# Power.net
KiCad netlist of a schematic drawn in Altium Designer
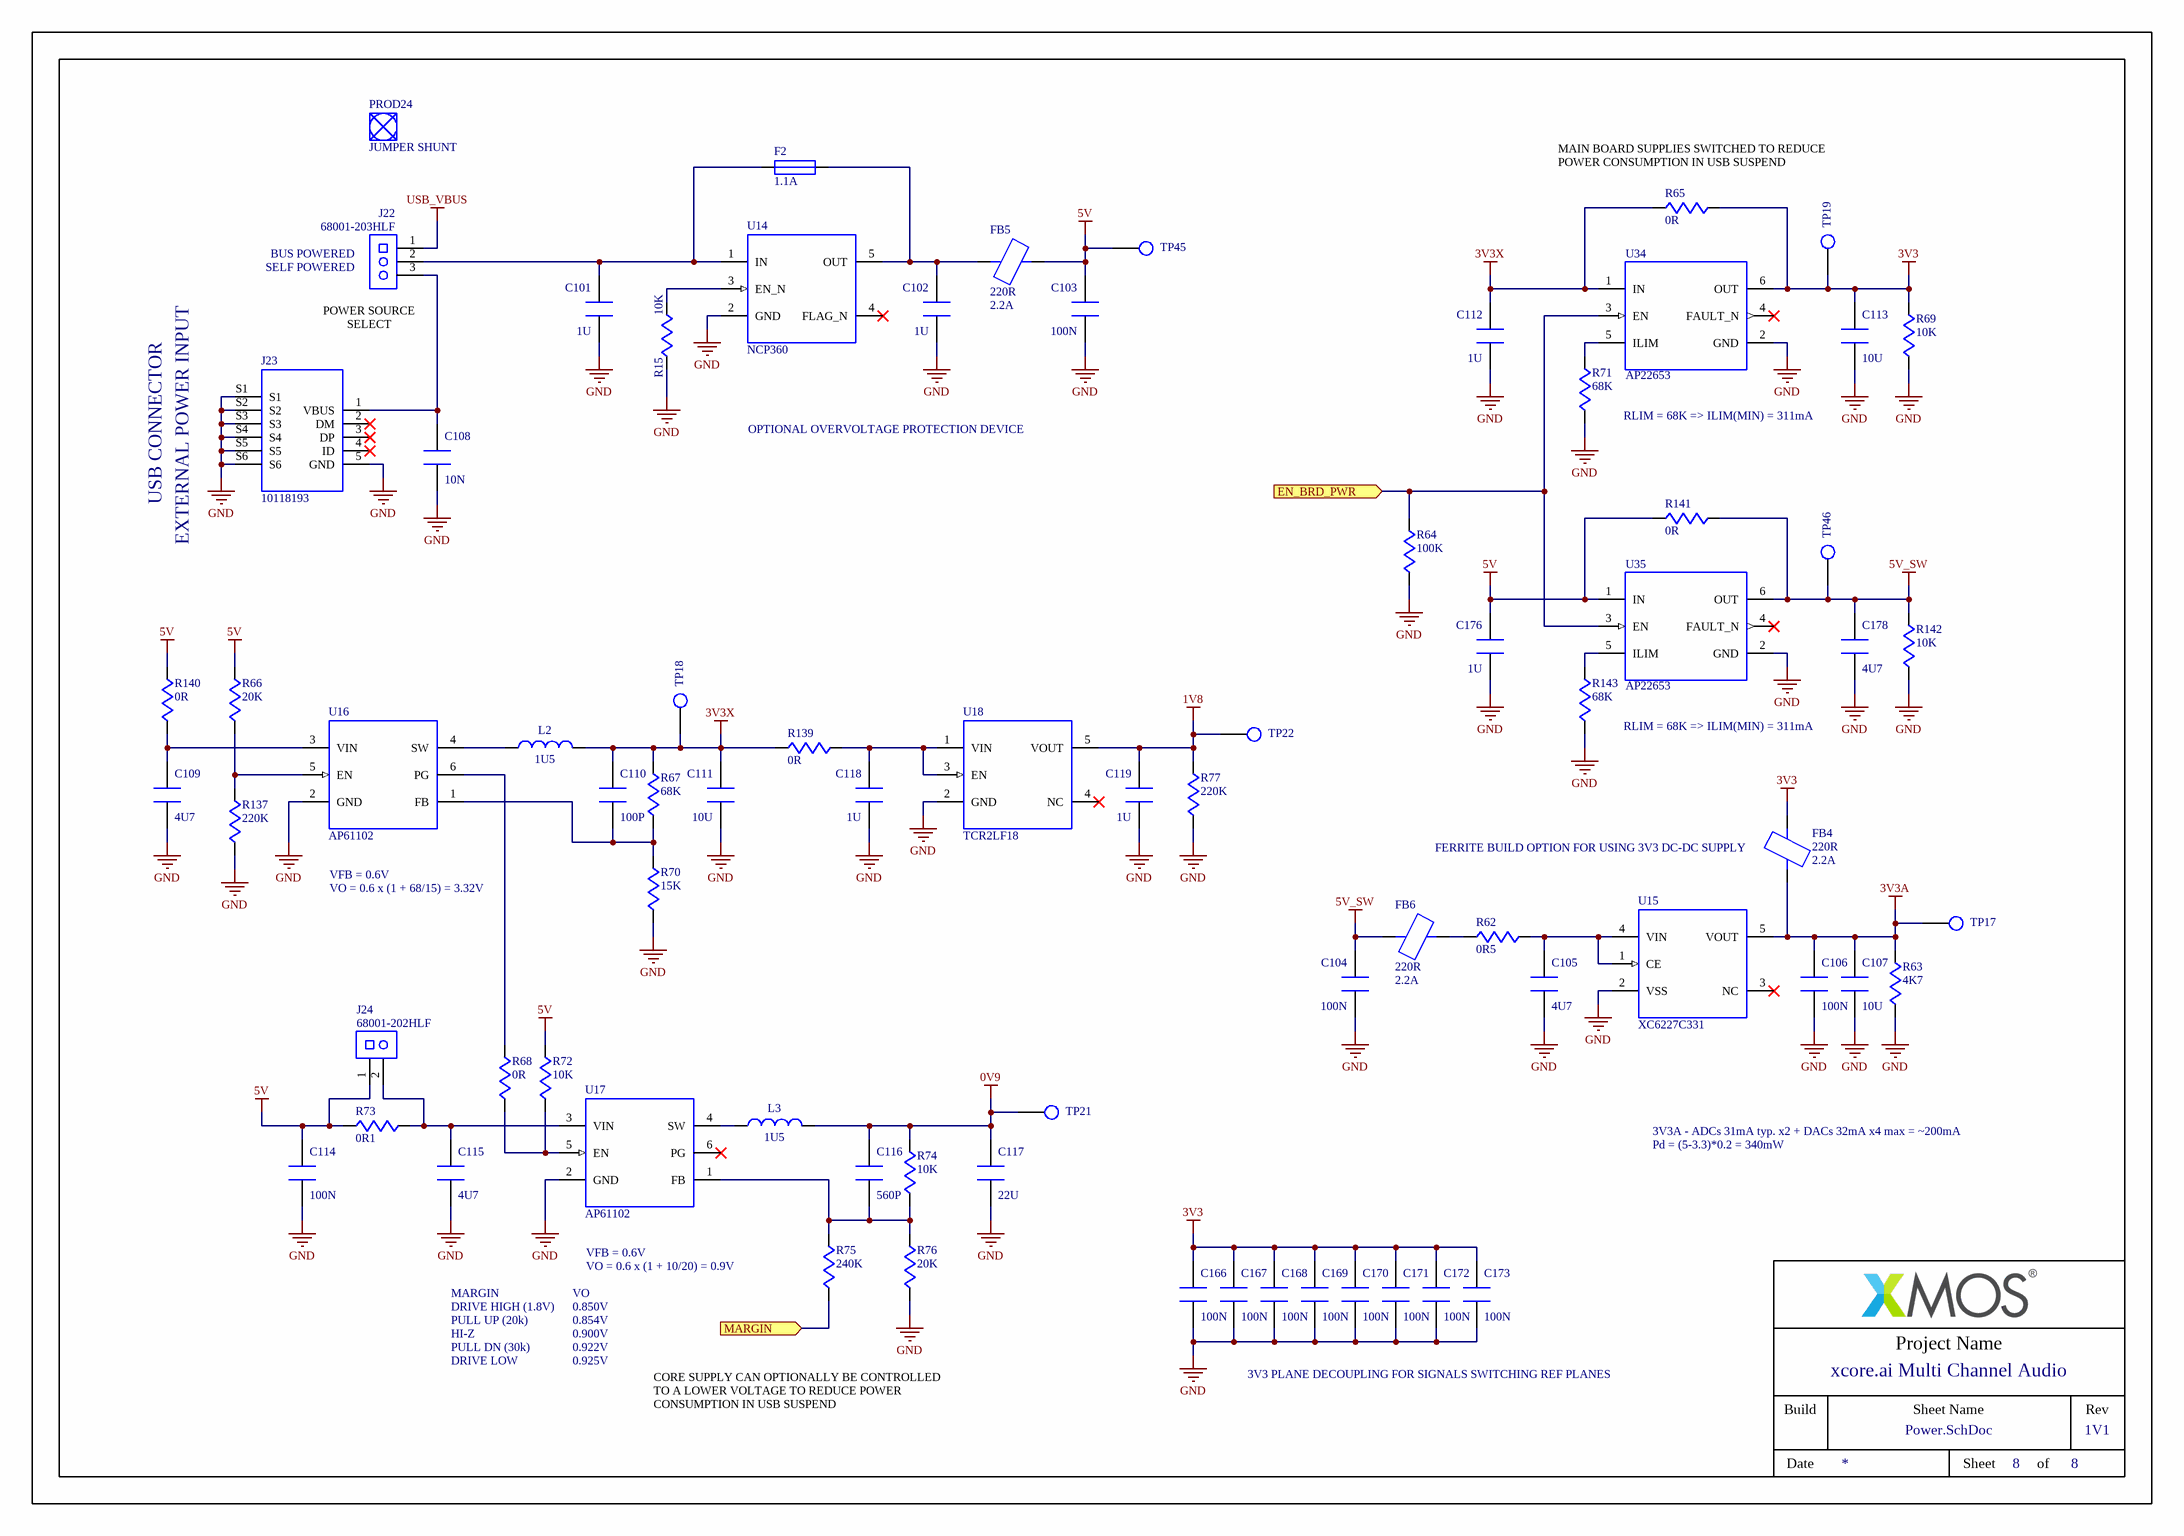
[diagram p0: Power.SchDoc]

(export (version "E")
  (design (tool "Eeschema 10.0.6"))
  (components
    (comp (ref "C101")
      (value "1U")
      (footprint "CAPC1005X55N")
      (description "CHIP CAPACITOR, CERAMIC, 1.0UF, 16V, 10%, X5R, 0402")
      (fields (field (name "PART NUMBER") "STD-06-0140") (field (name "TOLERANCE") "20%"))
      (libsource (lib "JG_StandardLibrary") (part "CAP_NP"))
    )
    (comp (ref "C102")
      (value "1U")
      (footprint "CAPC1005X55N")
      (description "CHIP CAPACITOR, CERAMIC, 1.0UF, 16V, 10%, X5R, 0402")
      (fields (field (name "PART NUMBER") "STD-06-0140") (field (name "TOLERANCE") "20%"))
      (libsource (lib "JG_StandardLibrary") (part "CAP_NP"))
    )
    (comp (ref "C103")
      (value "100N")
      (footprint "CAPC1005X55N")
      (description "CHIP CAPACITOR, CERAMIC, 100NF, 16V, 10%, X7R, 0402")
      (fields (field (name "PART NUMBER") "STD-06-0048") (field (name "TOLERANCE") "10%"))
      (libsource (lib "JG_StandardLibrary") (part "CAP_NP"))
    )
    (comp (ref "C104")
      (value "100N")
      (footprint "CAPC1005X55N")
      (description "CHIP CAPACITOR, CERAMIC, 100NF, 16V, 10%, X7R, 0402")
      (fields (field (name "PART NUMBER") "STD-06-0048") (field (name "TOLERANCE") "10%"))
      (libsource (lib "JG_StandardLibrary") (part "CAP_NP"))
    )
    (comp (ref "C105")
      (value "4U7")
      (footprint "CAPC1608X90N")
      (description "CHIP CAPACITOR, CERAMIC, 4.7UF, 16V, 10%, X5R, 0603")
      (fields (field (name "PART NUMBER") "STD-06-0151") (field (name "TOLERANCE") "10%"))
      (libsource (lib "JG_StandardLibrary") (part "CAP_NP"))
    )
    (comp (ref "C106")
      (value "100N")
      (footprint "CAPC1005X55N")
      (description "CHIP CAPACITOR, CERAMIC, 100NF, 16V, 10%, X7R, 0402")
      (fields (field (name "PART NUMBER") "STD-06-0048") (field (name "TOLERANCE") "10%"))
      (libsource (lib "JG_StandardLibrary") (part "CAP_NP"))
    )
    (comp (ref "C107")
      (value "10U")
      (footprint "CAPC1608X90N")
      (description "CHIP CAPACITOR, CERAMIC, 10UF, 10V, 20%, X5R, 0603")
      (fields (field (name "PART NUMBER") "GEN-03-0043") (field (name "TOLERANCE") "20%"))
      (libsource (lib "JG_GeneralLibrary") (part "CAP_NP"))
    )
    (comp (ref "C108")
      (value "10N")
      (footprint "CAPC1005X55N")
      (description "CHIP CAPACITOR, CERAMIC, 10NF, 50V, 10%, X7R, 0402")
      (fields (field (name "PART NUMBER") "STD-06-0042") (field (name "TOLERANCE") "10%"))
      (libsource (lib "JG_StandardLibrary") (part "CAP_NP"))
    )
    (comp (ref "C109")
      (value "4U7")
      (footprint "CAPC1608X90N")
      (description "CHIP CAPACITOR, CERAMIC, 4.7UF, 16V, 10%, X5R, 0603")
      (fields (field (name "PART NUMBER") "STD-06-0151") (field (name "TOLERANCE") "10%"))
      (libsource (lib "JG_StandardLibrary") (part "CAP_NP"))
    )
    (comp (ref "C110")
      (value "100P")
      (footprint "CAPC1005X55N")
      (description "CHIP CAPACITOR, CERAMIC, 100PF, 50V, 10%, X7R, 0402")
      (fields (field (name "PART NUMBER") "STD-06-0030") (field (name "TOLERANCE") "10%"))
      (libsource (lib "JG_StandardLibrary") (part "CAP_NP"))
    )
    (comp (ref "C111")
      (value "10U")
      (footprint "CAPC1608X90N")
      (description "CHIP CAPACITOR, CERAMIC, 10UF, 10V, 20%, X5R, 0603")
      (fields (field (name "PART NUMBER") "GEN-03-0043") (field (name "TOLERANCE") "20%"))
      (libsource (lib "JG_GeneralLibrary") (part "CAP_NP"))
    )
    (comp (ref "C112")
      (value "1U")
      (footprint "CAPC1005X55N")
      (description "CHIP CAPACITOR, CERAMIC, 1.0UF, 16V, 10%, X5R, 0402")
      (fields (field (name "PART NUMBER") "STD-06-0140") (field (name "TOLERANCE") "20%"))
      (libsource (lib "JG_StandardLibrary") (part "CAP_NP"))
    )
    (comp (ref "C113")
      (value "10U")
      (footprint "CAPC1608X90N")
      (description "CHIP CAPACITOR, CERAMIC, 10UF, 10V, 20%, X5R, 0603")
      (fields (field (name "PART NUMBER") "GEN-03-0043") (field (name "TOLERANCE") "20%"))
      (libsource (lib "JG_GeneralLibrary") (part "CAP_NP"))
    )
    (comp (ref "C114")
      (value "100N")
      (footprint "CAPC1005X55N")
      (description "CHIP CAPACITOR, CERAMIC, 100NF, 16V, 10%, X7R, 0402")
      (fields (field (name "PART NUMBER") "STD-06-0048") (field (name "TOLERANCE") "10%"))
      (libsource (lib "JG_StandardLibrary") (part "CAP_NP"))
    )
    (comp (ref "C115")
      (value "4U7")
      (footprint "CAPC1608X90N")
      (description "CHIP CAPACITOR, CERAMIC, 4.7UF, 16V, 10%, X5R, 0603")
      (fields (field (name "PART NUMBER") "STD-06-0151") (field (name "TOLERANCE") "10%"))
      (libsource (lib "JG_StandardLibrary") (part "CAP_NP"))
    )
    (comp (ref "C116")
      (value "560P")
      (footprint "CAPC1005X55N")
      (description "CHIP CAPACITOR, CERAMIC, 560PF, 50V, 5%, NP0, 0402")
      (fields (field (name "PART NUMBER") "STD-06-0147") (field (name "TOLERANCE") "5%"))
      (libsource (lib "JG_StandardLibrary") (part "CAP_NP"))
    )
    (comp (ref "C117")
      (value "22U")
      (footprint "CAPC1608X90N")
      (description "CHIP CAPACITOR, CERAMIC, 22UF, 6.3V, 20%, X5R, 0603")
      (fields (field (name "PART NUMBER") "GEN-03-0046") (field (name "TOLERANCE") "20%"))
      (libsource (lib "JG_GeneralLibrary") (part "CAP_NP"))
    )
    (comp (ref "C118")
      (value "1U")
      (footprint "CAPC1005X55N")
      (description "CHIP CAPACITOR, CERAMIC, 1.0UF, 16V, 10%, X5R, 0402")
      (fields (field (name "PART NUMBER") "STD-06-0140") (field (name "TOLERANCE") "20%"))
      (libsource (lib "JG_StandardLibrary") (part "CAP_NP"))
    )
    (comp (ref "C119")
      (value "1U")
      (footprint "CAPC1005X55N")
      (description "CHIP CAPACITOR, CERAMIC, 1.0UF, 16V, 10%, X5R, 0402")
      (fields (field (name "PART NUMBER") "STD-06-0140") (field (name "TOLERANCE") "20%"))
      (libsource (lib "JG_StandardLibrary") (part "CAP_NP"))
    )
    (comp (ref "C166")
      (value "100N")
      (footprint "CAPC1005X55N")
      (description "CHIP CAPACITOR, CERAMIC, 100NF, 16V, 10%, X7R, 0402")
      (fields (field (name "PART NUMBER") "STD-06-0048") (field (name "TOLERANCE") "10%"))
      (libsource (lib "JG_StandardLibrary") (part "CAP_NP"))
    )
    (comp (ref "C167")
      (value "100N")
      (footprint "CAPC1005X55N")
      (description "CHIP CAPACITOR, CERAMIC, 100NF, 16V, 10%, X7R, 0402")
      (fields (field (name "PART NUMBER") "STD-06-0048") (field (name "TOLERANCE") "10%"))
      (libsource (lib "JG_StandardLibrary") (part "CAP_NP"))
    )
    (comp (ref "C168")
      (value "100N")
      (footprint "CAPC1005X55N")
      (description "CHIP CAPACITOR, CERAMIC, 100NF, 16V, 10%, X7R, 0402")
      (fields (field (name "PART NUMBER") "STD-06-0048") (field (name "TOLERANCE") "10%"))
      (libsource (lib "JG_StandardLibrary") (part "CAP_NP"))
    )
    (comp (ref "C169")
      (value "100N")
      (footprint "CAPC1005X55N")
      (description "CHIP CAPACITOR, CERAMIC, 100NF, 16V, 10%, X7R, 0402")
      (fields (field (name "PART NUMBER") "STD-06-0048") (field (name "TOLERANCE") "10%"))
      (libsource (lib "JG_StandardLibrary") (part "CAP_NP"))
    )
    (comp (ref "C170")
      (value "100N")
      (footprint "CAPC1005X55N")
      (description "CHIP CAPACITOR, CERAMIC, 100NF, 16V, 10%, X7R, 0402")
      (fields (field (name "PART NUMBER") "STD-06-0048") (field (name "TOLERANCE") "10%"))
      (libsource (lib "JG_StandardLibrary") (part "CAP_NP"))
    )
    (comp (ref "C171")
      (value "100N")
      (footprint "CAPC1005X55N")
      (description "CHIP CAPACITOR, CERAMIC, 100NF, 16V, 10%, X7R, 0402")
      (fields (field (name "PART NUMBER") "STD-06-0048") (field (name "TOLERANCE") "10%"))
      (libsource (lib "JG_StandardLibrary") (part "CAP_NP"))
    )
    (comp (ref "C172")
      (value "100N")
      (footprint "CAPC1005X55N")
      (description "CHIP CAPACITOR, CERAMIC, 100NF, 16V, 10%, X7R, 0402")
      (fields (field (name "PART NUMBER") "STD-06-0048") (field (name "TOLERANCE") "10%"))
      (libsource (lib "JG_StandardLibrary") (part "CAP_NP"))
    )
    (comp (ref "C173")
      (value "100N")
      (footprint "CAPC1005X55N")
      (description "CHIP CAPACITOR, CERAMIC, 100NF, 16V, 10%, X7R, 0402")
      (fields (field (name "PART NUMBER") "STD-06-0048") (field (name "TOLERANCE") "10%"))
      (libsource (lib "JG_StandardLibrary") (part "CAP_NP"))
    )
    (comp (ref "C176")
      (value "1U")
      (footprint "CAPC1005X55N")
      (description "CHIP CAPACITOR, CERAMIC, 1.0UF, 16V, 10%, X5R, 0402")
      (fields (field (name "PART NUMBER") "STD-06-0140") (field (name "TOLERANCE") "20%"))
      (libsource (lib "JG_StandardLibrary") (part "CAP_NP"))
    )
    (comp (ref "C178")
      (value "4U7")
      (footprint "CAPC1608X90N")
      (description "CHIP CAPACITOR, CERAMIC, 4.7UF, 16V, 10%, X5R, 0603")
      (fields (field (name "PART NUMBER") "STD-06-0151") (field (name "TOLERANCE") "10%"))
      (libsource (lib "JG_StandardLibrary") (part "CAP_NP"))
    )
    (comp (ref "F2")
      (value "1.1A")
      (footprint "FUSC4632X150N")
      (description "Polyswitch Resettable Fuse, miniSMDC Series, 1.1A, 24V, SMD")
      (fields (field (name "PART NUMBER") "GEN-21-0008") (field (name "MANUFACTURER") "Littelfuse"))
      (libsource (lib "JG_GeneralLibrary") (part "FUSE"))
    )
    (comp (ref "FB4")
      (value "220R")
      (footprint "INDC1608X95N")
      (description "Ferrite Bead, 220R AT 100MHz, For Power Lines, AEC-Q200, 0603, 2.2A")
      (fields
        (field (name "PART NUMBER") "GEN-04-0018")
        (field (name "RATED CURRENT") "2.2A")
        (field (name "MANUFACTURER") "Murata")
      )
      (libsource (lib "JG_GeneralLibrary") (part "FERRITE"))
    )
    (comp (ref "FB5")
      (value "220R")
      (footprint "INDC1608X95N")
      (description "Ferrite Bead, 220R AT 100MHz, For Power Lines, AEC-Q200, 0603, 2.2A")
      (fields
        (field (name "PART NUMBER") "GEN-04-0018")
        (field (name "RATED CURRENT") "2.2A")
        (field (name "MANUFACTURER") "Murata")
      )
      (libsource (lib "JG_GeneralLibrary") (part "FERRITE"))
    )
    (comp (ref "FB6")
      (value "220R")
      (footprint "INDC1608X95N")
      (description "Ferrite Bead, 220R AT 100MHz, For Power Lines, AEC-Q200, 0603, 2.2A")
      (fields
        (field (name "PART NUMBER") "GEN-04-0018")
        (field (name "RATED CURRENT") "2.2A")
        (field (name "MANUFACTURER") "Murata")
      )
      (libsource (lib "JG_GeneralLibrary") (part "FERRITE"))
    )
    (comp (ref "J22")
      (value "68001-203HLF")
      (footprint "HDR_FCI_68001_203")
      (description "Pin Header, Male, Vertical, Through Hole, 3 Way, 1x3, 0.1 Inch Pitch")
      (fields (field (name "PART NUMBER") "GEN-01-0023") (field (name "MANUFACTURER") "FCI"))
      (libsource (lib "JG_GeneralLibrary") (part "PIN_HEADER_1X3"))
    )
    (comp (ref "J23")
      (value "10118193")
      (footprint "CON_FCI_10118193")
      (description "USB Micro B Receptacle, Right Angle, SMD w/2 DIP Legs")
      (fields (field (name "PART NUMBER") "GEN-01-0020") (field (name "MANUFACTURER") "FCI"))
      (libsource (lib "JG_GeneralLibrary") (part "FCI_10118193"))
    )
    (comp (ref "J24")
      (value "68001-202HLF")
      (footprint "HDR_FCI_68001_202")
      (description "Pin Header, Male, Vertical, Through Hole, 2 Way, 1x2, 0.1 Inch Pitch")
      (fields (field (name "PART NUMBER") "GEN-01-0011") (field (name "MANUFACTURER") "FCI"))
      (libsource (lib "JG_GeneralLibrary") (part "PIN_HEADER_1X2"))
    )
    (comp (ref "L2")
      (value "1U5")
      (footprint "INDC2520X120N")
      (description "Power Inductor, 1.5uH, 2.6A, 65mR DCR, 2.5x2.0x1.2mm, SMD")
      (fields (field (name "PART NUMBER") "GEN-05-0025") (field (name "TOLERANCE") "20%"))
      (libsource (lib "JG_GeneralLibrary") (part "INDUCTOR"))
    )
    (comp (ref "L3")
      (value "1U5")
      (footprint "INDC2520X120N")
      (description "Power Inductor, 1.5uH, 2.6A, 65mR DCR, 2.5x2.0x1.2mm, SMD")
      (fields (field (name "PART NUMBER") "GEN-05-0025") (field (name "TOLERANCE") "20%"))
      (libsource (lib "JG_GeneralLibrary") (part "INDUCTOR"))
    )
    (comp (ref "PROD24")
      (value "JUMPER SHUNT")
      (description "Jumper Shunt, Single Circuit, Open Type, 2.54mm Pitch, 6mm High, Gold Flash")
      (fields (field (name "PART NUMBER") "GEN-23-0011") (field (name "MANUFACTURER") "Sullins"))
      (libsource (lib "JG_GeneralLibrary") (part "PROD_ITEM"))
    )
    (comp (ref "R15")
      (value "10K")
      (footprint "RESC1608X55N")
      (description "CHIP RESISTOR, 10K OHM, 0.1W, 1%, 0603")
      (fields (field (name "PART NUMBER") "STD-02-0086") (field (name "TOLERANCE") "1%"))
      (libsource (lib "JG_StandardLibrary") (part "RES"))
    )
    (comp (ref "R62")
      (value "0R5")
      (footprint "RESC1608X55N")
      (description "CHIP RESISTOR, 0.5 OHM, 100mW, 1%, 0603")
      (fields (field (name "PART NUMBER") "GEN-02-0023") (field (name "TOLERANCE") "1%"))
      (libsource (lib "JG_GeneralLibrary") (part "RES"))
    )
    (comp (ref "R63")
      (value "4K7")
      (footprint "RESC1608X55N")
      (description "CHIP RESISTOR, 4.7K OHM, 0.1W, 1%, 0603")
      (fields (field (name "PART NUMBER") "STD-02-0078") (field (name "TOLERANCE") "1%"))
      (libsource (lib "JG_StandardLibrary") (part "RES"))
    )
    (comp (ref "R64")
      (value "100K")
      (footprint "RESC1608X55N")
      (description "CHIP RESISTOR, 100K OHM, 0.1W, 1%, 0603")
      (fields (field (name "PART NUMBER") "STD-02-0110") (field (name "TOLERANCE") "1%"))
      (libsource (lib "JG_StandardLibrary") (part "RES"))
    )
    (comp (ref "R65")
      (value "0R")
      (footprint "RESC1608X55N")
      (description "CHIP RESISTOR, ZERO OHM JUMPER, 1A, 0603")
      (fields (field (name "PART NUMBER") "STD-02-0001") (field (name "TOLERANCE") "NA"))
      (libsource (lib "JG_StandardLibrary") (part "RES"))
    )
    (comp (ref "R66")
      (value "20K")
      (footprint "RESC1608X55N")
      (description "CHIP RESISTOR, 20K OHM, 0.1W, 1%, 0603")
      (fields (field (name "PART NUMBER") "STD-02-0093") (field (name "TOLERANCE") "1%"))
      (libsource (lib "JG_StandardLibrary") (part "RES"))
    )
    (comp (ref "R67")
      (value "68K")
      (footprint "RESC1608X55N")
      (description "CHIP RESISTOR, 68K OHM, 0.1W, 1%, 0603")
      (fields (field (name "PART NUMBER") "STD-02-0106") (field (name "TOLERANCE") "1%"))
      (libsource (lib "JG_StandardLibrary") (part "RES"))
    )
    (comp (ref "R68")
      (value "0R")
      (footprint "RESC1608X55N")
      (description "CHIP RESISTOR, ZERO OHM JUMPER, 1A, 0603")
      (fields (field (name "PART NUMBER") "STD-02-0001") (field (name "TOLERANCE") "NA"))
      (libsource (lib "JG_StandardLibrary") (part "RES"))
    )
    (comp (ref "R69")
      (value "10K")
      (footprint "RESC1608X55N")
      (description "CHIP RESISTOR, 10K OHM, 0.1W, 1%, 0603")
      (fields (field (name "PART NUMBER") "STD-02-0086") (field (name "TOLERANCE") "1%"))
      (libsource (lib "JG_StandardLibrary") (part "RES"))
    )
    (comp (ref "R70")
      (value "15K")
      (footprint "RESC1608X55N")
      (description "CHIP RESISTOR, 15K OHM, 0.1W, 1%, 0603")
      (fields (field (name "PART NUMBER") "STD-02-0090") (field (name "TOLERANCE") "1%"))
      (libsource (lib "JG_StandardLibrary") (part "RES"))
    )
    (comp (ref "R71")
      (value "68K")
      (footprint "RESC1608X55N")
      (description "CHIP RESISTOR, 68K OHM, 0.1W, 1%, 0603")
      (fields (field (name "PART NUMBER") "STD-02-0106") (field (name "TOLERANCE") "1%"))
      (libsource (lib "JG_StandardLibrary") (part "RES"))
    )
    (comp (ref "R72")
      (value "10K")
      (footprint "RESC1608X55N")
      (description "CHIP RESISTOR, 10K OHM, 0.1W, 1%, 0603")
      (fields (field (name "PART NUMBER") "STD-02-0086") (field (name "TOLERANCE") "1%"))
      (libsource (lib "JG_StandardLibrary") (part "RES"))
    )
    (comp (ref "R73")
      (value "0R1")
      (footprint "RESC1608X55N")
      (description "CHIP RESISTOR, 0.1 OHM, 100mW, 1%, 0603")
      (fields (field (name "PART NUMBER") "GEN-02-0024") (field (name "TOLERANCE") "1%"))
      (libsource (lib "JG_GeneralLibrary") (part "RES"))
    )
    (comp (ref "R74")
      (value "10K")
      (footprint "RESC1608X55N")
      (description "CHIP RESISTOR, 10K OHM, 0.1W, 1%, 0603")
      (fields (field (name "PART NUMBER") "STD-02-0086") (field (name "TOLERANCE") "1%"))
      (libsource (lib "JG_StandardLibrary") (part "RES"))
    )
    (comp (ref "R75")
      (value "240K")
      (footprint "RESC1608X55N")
      (description "CHIP RESISTOR, 240K OHM, 0.1W, 1%, 0603")
      (fields (field (name "PART NUMBER") "STD-02-0119") (field (name "TOLERANCE") "1%"))
      (libsource (lib "JG_StandardLibrary") (part "RES"))
    )
    (comp (ref "R76")
      (value "20K")
      (footprint "RESC1608X55N")
      (description "CHIP RESISTOR, 20K OHM, 0.1W, 1%, 0603")
      (fields (field (name "PART NUMBER") "STD-02-0093") (field (name "TOLERANCE") "1%"))
      (libsource (lib "JG_StandardLibrary") (part "RES"))
    )
    (comp (ref "R77")
      (value "220K")
      (footprint "RESC1608X55N")
      (description "CHIP RESISTOR, 220K OHM, 0.1W, 1%, 0603")
      (fields (field (name "PART NUMBER") "STD-02-0118") (field (name "TOLERANCE") "1%"))
      (libsource (lib "JG_StandardLibrary") (part "RES"))
    )
    (comp (ref "R137")
      (value "220K")
      (footprint "RESC1608X55N")
      (description "CHIP RESISTOR, 220K OHM, 0.1W, 1%, 0603")
      (fields (field (name "PART NUMBER") "STD-02-0118") (field (name "TOLERANCE") "1%"))
      (libsource (lib "JG_StandardLibrary") (part "RES"))
    )
    (comp (ref "R139")
      (value "0R")
      (footprint "RESC1608X55N")
      (description "CHIP RESISTOR, ZERO OHM JUMPER, 1A, 0603")
      (fields (field (name "PART NUMBER") "STD-02-0001") (field (name "TOLERANCE") "NA"))
      (libsource (lib "JG_StandardLibrary") (part "RES"))
    )
    (comp (ref "R140")
      (value "0R")
      (footprint "RESC1608X55N")
      (description "CHIP RESISTOR, ZERO OHM JUMPER, 1A, 0603")
      (fields (field (name "PART NUMBER") "STD-02-0001") (field (name "TOLERANCE") "NA"))
      (libsource (lib "JG_StandardLibrary") (part "RES"))
    )
    (comp (ref "R141")
      (value "0R")
      (footprint "RESC1608X55N")
      (description "CHIP RESISTOR, ZERO OHM JUMPER, 1A, 0603")
      (fields (field (name "PART NUMBER") "STD-02-0001") (field (name "TOLERANCE") "NA"))
      (libsource (lib "JG_StandardLibrary") (part "RES"))
    )
    (comp (ref "R142")
      (value "10K")
      (footprint "RESC1608X55N")
      (description "CHIP RESISTOR, 10K OHM, 0.1W, 1%, 0603")
      (fields (field (name "PART NUMBER") "STD-02-0086") (field (name "TOLERANCE") "1%"))
      (libsource (lib "JG_StandardLibrary") (part "RES"))
    )
    (comp (ref "R143")
      (value "68K")
      (footprint "RESC1608X55N")
      (description "CHIP RESISTOR, 68K OHM, 0.1W, 1%, 0603")
      (fields (field (name "PART NUMBER") "STD-02-0106") (field (name "TOLERANCE") "1%"))
      (libsource (lib "JG_StandardLibrary") (part "RES"))
    )
    (comp (ref "TP17")
      (value "TESTPOINT")
      (footprint "TESTPOINT_THRU")
      (description "Testpoint, Through Hole")
      (fields (field (name "PART NUMBER") "GEN-24-0002") (field (name "MANUFACTURER") "NA"))
      (libsource (lib "JG_GeneralLibrary") (part "TESTPOINT"))
    )
    (comp (ref "TP18")
      (value "TESTPOINT")
      (footprint "TESTPOINT_THRU")
      (description "Testpoint, Through Hole")
      (fields (field (name "PART NUMBER") "GEN-24-0002") (field (name "MANUFACTURER") "NA"))
      (libsource (lib "JG_GeneralLibrary") (part "TESTPOINT"))
    )
    (comp (ref "TP19")
      (value "TESTPOINT")
      (footprint "TESTPOINT_THRU")
      (description "Testpoint, Through Hole")
      (fields (field (name "PART NUMBER") "GEN-24-0002") (field (name "MANUFACTURER") "NA"))
      (libsource (lib "JG_GeneralLibrary") (part "TESTPOINT"))
    )
    (comp (ref "TP21")
      (value "TESTPOINT")
      (footprint "TESTPOINT_THRU")
      (description "Testpoint, Through Hole")
      (fields (field (name "PART NUMBER") "GEN-24-0002") (field (name "MANUFACTURER") "NA"))
      (libsource (lib "JG_GeneralLibrary") (part "TESTPOINT"))
    )
    (comp (ref "TP22")
      (value "TESTPOINT")
      (footprint "TESTPOINT_THRU")
      (description "Testpoint, Through Hole")
      (fields (field (name "PART NUMBER") "GEN-24-0002") (field (name "MANUFACTURER") "NA"))
      (libsource (lib "JG_GeneralLibrary") (part "TESTPOINT"))
    )
    (comp (ref "TP45")
      (value "TESTPOINT")
      (footprint "TESTPOINT_THRU")
      (description "Testpoint, Through Hole")
      (fields (field (name "PART NUMBER") "GEN-24-0002") (field (name "MANUFACTURER") "NA"))
      (libsource (lib "JG_GeneralLibrary") (part "TESTPOINT"))
    )
    (comp (ref "TP46")
      (value "TESTPOINT")
      (footprint "TESTPOINT_THRU")
      (description "Testpoint, Through Hole")
      (fields (field (name "PART NUMBER") "GEN-24-0002") (field (name "MANUFACTURER") "NA"))
      (libsource (lib "JG_GeneralLibrary") (part "TESTPOINT"))
    )
    (comp (ref "U14")
      (value "NCP360")
      (footprint "SOT23-5P95_275X110L40X37N")
      (description "USB Positive Overvoltage Protection Controller, Internal P-FET, OVLO 6.25V, TSOT23-5")
      (fields (field (name "PART NUMBER") "GEN-14-0068") (field (name "MANUFACTURER") "ON Semiconductor"))
      (libsource (lib "JG_GeneralLibrary") (part "ONSEMI_NCP361_TSOP"))
    )
    (comp (ref "U15")
      (value "XC6227C331")
      (footprint "TOREX_SOT_89_5")
      (description "Voltage Regulator, Linear, Fixed, 3V3, 700mA, w/enable, SOT89-5")
      (fields (field (name "PART NUMBER") "GEN-14-0070") (field (name "MANUFACTURER") "Torex Semiconductor"))
      (libsource (lib "JG_GeneralLibrary") (part "TOREX_XC6227_SOT89_5"))
    )
    (comp (ref "U16")
      (value "AP61102")
      (footprint "ICSOFL6P50_160X160X60L30X21N")
      (description "DC-DC Synchronous Buck Converter, Adjustable, PFM/PWM, Power Good, 2.2MHz, 1A, SOT563")
      (fields (field (name "PART NUMBER") "GEN-14-0064") (field (name "MANUFACTURER") "Diodes Incorporated"))
      (libsource (lib "JG_GeneralLibrary") (part "DIODES_AP61102"))
    )
    (comp (ref "U17")
      (value "AP61102")
      (footprint "ICSOFL6P50_160X160X60L30X21N")
      (description "DC-DC Synchronous Buck Converter, Adjustable, PFM/PWM, Power Good, 2.2MHz, 1A, SOT563")
      (fields (field (name "PART NUMBER") "GEN-14-0064") (field (name "MANUFACTURER") "Diodes Incorporated"))
      (libsource (lib "JG_GeneralLibrary") (part "DIODES_AP61102"))
    )
    (comp (ref "U18")
      (value "TCR2LF18")
      (footprint "SOT23-5P95_275X110L40X37N")
      (description "Voltage Regulator, Linear, Fixed, 1V8, 200mA, Low Iq=2uA, Output Active Discharge, TSOT23-5")
      (fields (field (name "PART NUMBER") "GEN-14-0066") (field (name "MANUFACTURER") "Toshiba"))
      (libsource (lib "JG_GeneralLibrary") (part "VREG_FIXED_5_A"))
    )
    (comp (ref "U34")
      (value "AP22653")
      (footprint "SOT95P280X145-6N")
      (description "Precision Adjustable Current Limited Load Switch, 3.0 - 5.5V, 2.1A max, Active High Enable, SOT26")
      (fields (field (name "PART NUMBER") "GEN-14-0072") (field (name "MANUFACTURER") "Diodes Incorporated"))
      (libsource (lib "JG_GeneralLibrary") (part "DIODES_AP22653_SOT26"))
    )
    (comp (ref "U35")
      (value "AP22653")
      (footprint "SOT95P280X145-6N")
      (description "Precision Adjustable Current Limited Load Switch, 3.0 - 5.5V, 2.1A max, Active High Enable, SOT26")
      (fields (field (name "PART NUMBER") "GEN-14-0072") (field (name "MANUFACTURER") "Diodes Incorporated"))
      (libsource (lib "JG_GeneralLibrary") (part "DIODES_AP22653_SOT26"))
    )
  )
  (nets
    (net (code "1") (name "/EN_BRD_PWR") (class "Default")
      (node (ref "R64") (pin "2") (pinfunction "2_2") (pintype "passive"))
      (node (ref "U34") (pin "3") (pinfunction "EN_3") (pintype "input"))
      (node (ref "U35") (pin "3") (pinfunction "EN_3") (pintype "input"))
    )
    (net (code "2") (name "/MARGIN") (class "Default")
      (node (ref "R75") (pin "1") (pinfunction "1_1") (pintype "passive"))
    )
    (net (code "3") (name "0V9") (class "Default")
      (node (ref "C116") (pin "1") (pinfunction "1_1") (pintype "passive"))
      (node (ref "C117") (pin "1") (pinfunction "1_1") (pintype "passive"))
      (node (ref "L3") (pin "2") (pinfunction "2_2") (pintype "passive"))
      (node (ref "R74") (pin "2") (pinfunction "2_2") (pintype "passive"))
      (node (ref "TP21") (pin "1") (pinfunction "1_1") (pintype "passive"))
    )
    (net (code "4") (name "1V8") (class "Default")
      (node (ref "C119") (pin "1") (pinfunction "1_1") (pintype "passive"))
      (node (ref "R77") (pin "2") (pinfunction "2_2") (pintype "passive"))
      (node (ref "TP22") (pin "1") (pinfunction "1_1") (pintype "passive"))
      (node (ref "U18") (pin "5") (pinfunction "VOUT_5") (pintype "power_in"))
    )
    (net (code "5") (name "3V3") (class "Default")
      (node (ref "C113") (pin "1") (pinfunction "1_1") (pintype "passive"))
      (node (ref "C166") (pin "1") (pinfunction "1_1") (pintype "passive"))
      (node (ref "C167") (pin "1") (pinfunction "1_1") (pintype "passive"))
      (node (ref "C168") (pin "1") (pinfunction "1_1") (pintype "passive"))
      (node (ref "C169") (pin "1") (pinfunction "1_1") (pintype "passive"))
      (node (ref "C170") (pin "1") (pinfunction "1_1") (pintype "passive"))
      (node (ref "C171") (pin "1") (pinfunction "1_1") (pintype "passive"))
      (node (ref "C172") (pin "1") (pinfunction "1_1") (pintype "passive"))
      (node (ref "C173") (pin "1") (pinfunction "1_1") (pintype "passive"))
      (node (ref "FB4") (pin "2") (pinfunction "2_2") (pintype "passive"))
      (node (ref "R65") (pin "2") (pinfunction "2_2") (pintype "passive"))
      (node (ref "R69") (pin "2") (pinfunction "2_2") (pintype "passive"))
      (node (ref "TP19") (pin "1") (pinfunction "1_1") (pintype "passive"))
      (node (ref "U34") (pin "6") (pinfunction "OUT_6") (pintype "power_in"))
    )
    (net (code "6") (name "3V3A") (class "Default")
      (node (ref "C106") (pin "1") (pinfunction "1_1") (pintype "passive"))
      (node (ref "C107") (pin "1") (pinfunction "1_1") (pintype "passive"))
      (node (ref "FB4") (pin "1") (pinfunction "1_1") (pintype "passive"))
      (node (ref "R63") (pin "2") (pinfunction "2_2") (pintype "passive"))
      (node (ref "TP17") (pin "1") (pinfunction "1_1") (pintype "passive"))
      (node (ref "U15") (pin "5") (pinfunction "VOUT_5") (pintype "passive"))
    )
    (net (code "7") (name "3V3X") (class "Default")
      (node (ref "C110") (pin "1") (pinfunction "1_1") (pintype "passive"))
      (node (ref "C111") (pin "1") (pinfunction "1_1") (pintype "passive"))
      (node (ref "C112") (pin "1") (pinfunction "1_1") (pintype "passive"))
      (node (ref "L2") (pin "2") (pinfunction "2_2") (pintype "passive"))
      (node (ref "R139") (pin "1") (pinfunction "1_1") (pintype "passive"))
      (node (ref "R65") (pin "1") (pinfunction "1_1") (pintype "passive"))
      (node (ref "R67") (pin "2") (pinfunction "2_2") (pintype "passive"))
      (node (ref "TP18") (pin "1") (pinfunction "1_1") (pintype "passive"))
      (node (ref "U34") (pin "1") (pinfunction "IN_1") (pintype "power_in"))
    )
    (net (code "8") (name "5V") (class "Default")
      (node (ref "C103") (pin "1") (pinfunction "1_1") (pintype "passive"))
      (node (ref "C114") (pin "1") (pinfunction "1_1") (pintype "passive"))
      (node (ref "C176") (pin "1") (pinfunction "1_1") (pintype "passive"))
      (node (ref "FB5") (pin "2") (pinfunction "2_2") (pintype "passive"))
      (node (ref "J24") (pin "1") (pinfunction "1_1") (pintype "passive"))
      (node (ref "R140") (pin "2") (pinfunction "2_2") (pintype "passive"))
      (node (ref "R141") (pin "1") (pinfunction "1_1") (pintype "passive"))
      (node (ref "R66") (pin "2") (pinfunction "2_2") (pintype "passive"))
      (node (ref "R72") (pin "2") (pinfunction "2_2") (pintype "passive"))
      (node (ref "R73") (pin "1") (pinfunction "1_1") (pintype "passive"))
      (node (ref "TP45") (pin "1") (pinfunction "1_1") (pintype "passive"))
      (node (ref "U35") (pin "1") (pinfunction "IN_1") (pintype "power_in"))
    )
    (net (code "9") (name "5V_SW") (class "Default")
      (node (ref "C104") (pin "1") (pinfunction "1_1") (pintype "passive"))
      (node (ref "C178") (pin "1") (pinfunction "1_1") (pintype "passive"))
      (node (ref "FB6") (pin "1") (pinfunction "1_1") (pintype "passive"))
      (node (ref "R141") (pin "2") (pinfunction "2_2") (pintype "passive"))
      (node (ref "R142") (pin "2") (pinfunction "2_2") (pintype "passive"))
      (node (ref "TP46") (pin "1") (pinfunction "1_1") (pintype "passive"))
      (node (ref "U35") (pin "6") (pinfunction "OUT_6") (pintype "power_in"))
    )
    (net (code "10") (name "GND") (class "Default")
      (node (ref "C101") (pin "2") (pinfunction "2_2") (pintype "passive"))
      (node (ref "C102") (pin "2") (pinfunction "2_2") (pintype "passive"))
      (node (ref "C103") (pin "2") (pinfunction "2_2") (pintype "passive"))
      (node (ref "C104") (pin "2") (pinfunction "2_2") (pintype "passive"))
      (node (ref "C105") (pin "2") (pinfunction "2_2") (pintype "passive"))
      (node (ref "C106") (pin "2") (pinfunction "2_2") (pintype "passive"))
      (node (ref "C107") (pin "2") (pinfunction "2_2") (pintype "passive"))
      (node (ref "C108") (pin "2") (pinfunction "2_2") (pintype "passive"))
      (node (ref "C109") (pin "2") (pinfunction "2_2") (pintype "passive"))
      (node (ref "C111") (pin "2") (pinfunction "2_2") (pintype "passive"))
      (node (ref "C112") (pin "2") (pinfunction "2_2") (pintype "passive"))
      (node (ref "C113") (pin "2") (pinfunction "2_2") (pintype "passive"))
      (node (ref "C114") (pin "2") (pinfunction "2_2") (pintype "passive"))
      (node (ref "C115") (pin "2") (pinfunction "2_2") (pintype "passive"))
      (node (ref "C117") (pin "2") (pinfunction "2_2") (pintype "passive"))
      (node (ref "C118") (pin "2") (pinfunction "2_2") (pintype "passive"))
      (node (ref "C119") (pin "2") (pinfunction "2_2") (pintype "passive"))
      (node (ref "C166") (pin "2") (pinfunction "2_2") (pintype "passive"))
      (node (ref "C167") (pin "2") (pinfunction "2_2") (pintype "passive"))
      (node (ref "C168") (pin "2") (pinfunction "2_2") (pintype "passive"))
      (node (ref "C169") (pin "2") (pinfunction "2_2") (pintype "passive"))
      (node (ref "C170") (pin "2") (pinfunction "2_2") (pintype "passive"))
      (node (ref "C171") (pin "2") (pinfunction "2_2") (pintype "passive"))
      (node (ref "C172") (pin "2") (pinfunction "2_2") (pintype "passive"))
      (node (ref "C173") (pin "2") (pinfunction "2_2") (pintype "passive"))
      (node (ref "C176") (pin "2") (pinfunction "2_2") (pintype "passive"))
      (node (ref "C178") (pin "2") (pinfunction "2_2") (pintype "passive"))
      (node (ref "J23") (pin "5") (pinfunction "GND_5") (pintype "passive"))
      (node (ref "J23") (pin "S1") (pinfunction "S1_S1") (pintype "passive"))
      (node (ref "J23") (pin "S2") (pinfunction "S2_S2") (pintype "passive"))
      (node (ref "J23") (pin "S3") (pinfunction "S3_S3") (pintype "passive"))
      (node (ref "J23") (pin "S4") (pinfunction "S4_S4") (pintype "passive"))
      (node (ref "J23") (pin "S5") (pinfunction "S5_S5") (pintype "passive"))
      (node (ref "J23") (pin "S6") (pinfunction "S6_S6") (pintype "passive"))
      (node (ref "R137") (pin "1") (pinfunction "1_1") (pintype "passive"))
      (node (ref "R142") (pin "1") (pinfunction "1_1") (pintype "passive"))
      (node (ref "R143") (pin "1") (pinfunction "1_1") (pintype "passive"))
      (node (ref "R15") (pin "1") (pinfunction "1_1") (pintype "passive"))
      (node (ref "R63") (pin "1") (pinfunction "1_1") (pintype "passive"))
      (node (ref "R64") (pin "1") (pinfunction "1_1") (pintype "passive"))
      (node (ref "R69") (pin "1") (pinfunction "1_1") (pintype "passive"))
      (node (ref "R70") (pin "1") (pinfunction "1_1") (pintype "passive"))
      (node (ref "R71") (pin "1") (pinfunction "1_1") (pintype "passive"))
      (node (ref "R76") (pin "1") (pinfunction "1_1") (pintype "passive"))
      (node (ref "R77") (pin "1") (pinfunction "1_1") (pintype "passive"))
      (node (ref "U14") (pin "2") (pinfunction "GND_2") (pintype "power_in"))
      (node (ref "U15") (pin "2") (pinfunction "VSS_2") (pintype "power_in"))
      (node (ref "U16") (pin "2") (pinfunction "GND_2") (pintype "power_in"))
      (node (ref "U17") (pin "2") (pinfunction "GND_2") (pintype "power_in"))
      (node (ref "U18") (pin "2") (pinfunction "GND_2") (pintype "power_in"))
      (node (ref "U34") (pin "2") (pinfunction "GND_2") (pintype "power_in"))
      (node (ref "U35") (pin "2") (pinfunction "GND_2") (pintype "power_in"))
    )
    (net (code "11") (name "Net-(F2-T1)") (class "Default")
      (node (ref "C101") (pin "1") (pinfunction "1_1") (pintype "passive"))
      (node (ref "F2") (pin "1") (pinfunction "T1_1") (pintype "passive"))
      (node (ref "J22") (pin "2") (pinfunction "2_2") (pintype "passive"))
      (node (ref "U14") (pin "1") (pinfunction "IN_1") (pintype "power_in"))
    )
    (net (code "12") (name "Net-(F2-T2)") (class "Default")
      (node (ref "C102") (pin "1") (pinfunction "1_1") (pintype "passive"))
      (node (ref "F2") (pin "2") (pinfunction "T2_2") (pintype "passive"))
      (node (ref "FB5") (pin "1") (pinfunction "1_1") (pintype "passive"))
      (node (ref "U14") (pin "5") (pinfunction "OUT_5") (pintype "power_in"))
    )
    (net (code "13") (name "Net-(FB6-Pad2)") (class "Default")
      (node (ref "FB6") (pin "2") (pinfunction "2_2") (pintype "passive"))
      (node (ref "R62") (pin "1") (pinfunction "1_1") (pintype "passive"))
    )
    (net (code "14") (name "Net-(J23-VBUS)") (class "Default")
      (node (ref "C108") (pin "1") (pinfunction "1_1") (pintype "passive"))
      (node (ref "J22") (pin "3") (pinfunction "3_3") (pintype "passive"))
      (node (ref "J23") (pin "1") (pinfunction "VBUS_1") (pintype "passive"))
    )
    (net (code "15") (name "Net-(U14-EN_N)") (class "Default")
      (node (ref "R15") (pin "2") (pinfunction "2_2") (pintype "passive"))
      (node (ref "U14") (pin "3") (pinfunction "EN_N_3") (pintype "input"))
    )
    (net (code "16") (name "Net-(U15-CE)") (class "Default")
      (node (ref "C105") (pin "1") (pinfunction "1_1") (pintype "passive"))
      (node (ref "R62") (pin "2") (pinfunction "2_2") (pintype "passive"))
      (node (ref "U15") (pin "1") (pinfunction "CE_1") (pintype "input"))
      (node (ref "U15") (pin "4") (pinfunction "VIN_4") (pintype "passive"))
    )
    (net (code "17") (name "Net-(U16-EN)") (class "Default")
      (node (ref "R137") (pin "2") (pinfunction "2_2") (pintype "passive"))
      (node (ref "R66") (pin "1") (pinfunction "1_1") (pintype "passive"))
      (node (ref "U16") (pin "5") (pinfunction "EN_5") (pintype "input"))
    )
    (net (code "18") (name "Net-(U16-FB)") (class "Default")
      (node (ref "C110") (pin "2") (pinfunction "2_2") (pintype "passive"))
      (node (ref "R67") (pin "1") (pinfunction "1_1") (pintype "passive"))
      (node (ref "R70") (pin "2") (pinfunction "2_2") (pintype "passive"))
      (node (ref "U16") (pin "1") (pinfunction "FB_1") (pintype "passive"))
    )
    (net (code "19") (name "Net-(U16-PG)") (class "Default")
      (node (ref "R68") (pin "2") (pinfunction "2_2") (pintype "passive"))
      (node (ref "U16") (pin "6") (pinfunction "PG_6") (pintype "passive"))
    )
    (net (code "20") (name "Net-(U16-SW)") (class "Default")
      (node (ref "L2") (pin "1") (pinfunction "1_1") (pintype "passive"))
      (node (ref "U16") (pin "4") (pinfunction "SW_4") (pintype "passive"))
    )
    (net (code "21") (name "Net-(U16-VIN)") (class "Default")
      (node (ref "C109") (pin "1") (pinfunction "1_1") (pintype "passive"))
      (node (ref "R140") (pin "1") (pinfunction "1_1") (pintype "passive"))
      (node (ref "U16") (pin "3") (pinfunction "VIN_3") (pintype "power_in"))
    )
    (net (code "22") (name "Net-(U17-EN)") (class "Default")
      (node (ref "R68") (pin "1") (pinfunction "1_1") (pintype "passive"))
      (node (ref "R72") (pin "1") (pinfunction "1_1") (pintype "passive"))
      (node (ref "U17") (pin "5") (pinfunction "EN_5") (pintype "input"))
    )
    (net (code "23") (name "Net-(U17-FB)") (class "Default")
      (node (ref "C116") (pin "2") (pinfunction "2_2") (pintype "passive"))
      (node (ref "R74") (pin "1") (pinfunction "1_1") (pintype "passive"))
      (node (ref "R75") (pin "2") (pinfunction "2_2") (pintype "passive"))
      (node (ref "R76") (pin "2") (pinfunction "2_2") (pintype "passive"))
      (node (ref "U17") (pin "1") (pinfunction "FB_1") (pintype "passive"))
    )
    (net (code "24") (name "Net-(U17-SW)") (class "Default")
      (node (ref "L3") (pin "1") (pinfunction "1_1") (pintype "passive"))
      (node (ref "U17") (pin "4") (pinfunction "SW_4") (pintype "passive"))
    )
    (net (code "25") (name "Net-(U17-VIN)") (class "Default")
      (node (ref "C115") (pin "1") (pinfunction "1_1") (pintype "passive"))
      (node (ref "J24") (pin "2") (pinfunction "2_2") (pintype "passive"))
      (node (ref "R73") (pin "2") (pinfunction "2_2") (pintype "passive"))
      (node (ref "U17") (pin "3") (pinfunction "VIN_3") (pintype "power_in"))
    )
    (net (code "26") (name "Net-(U18-EN)") (class "Default")
      (node (ref "C118") (pin "1") (pinfunction "1_1") (pintype "passive"))
      (node (ref "R139") (pin "2") (pinfunction "2_2") (pintype "passive"))
      (node (ref "U18") (pin "1") (pinfunction "VIN_1") (pintype "power_in"))
      (node (ref "U18") (pin "3") (pinfunction "EN_3") (pintype "input"))
    )
    (net (code "27") (name "Net-(U34-ILIM)") (class "Default")
      (node (ref "R71") (pin "2") (pinfunction "2_2") (pintype "passive"))
      (node (ref "U34") (pin "5") (pinfunction "ILIM_5") (pintype "passive"))
    )
    (net (code "28") (name "Net-(U35-ILIM)") (class "Default")
      (node (ref "R143") (pin "2") (pinfunction "2_2") (pintype "passive"))
      (node (ref "U35") (pin "5") (pinfunction "ILIM_5") (pintype "passive"))
    )
    (net (code "29") (name "USB_VBUS") (class "Default")
      (node (ref "J22") (pin "1") (pinfunction "1_1") (pintype "passive"))
    )
    (net (code "30") (name "unconnected-(J23-DM-Pad2)") (class "Default")
      (node (ref "J23") (pin "2") (pinfunction "DM_2") (pintype "passive+no_connect"))
    )
    (net (code "31") (name "unconnected-(J23-DP-Pad3)") (class "Default")
      (node (ref "J23") (pin "3") (pinfunction "DP_3") (pintype "passive+no_connect"))
    )
    (net (code "32") (name "unconnected-(J23-ID-Pad4)") (class "Default")
      (node (ref "J23") (pin "4") (pinfunction "ID_4") (pintype "passive+no_connect"))
    )
    (net (code "33") (name "unconnected-(U14-FLAG_N-Pad4)") (class "Default")
      (node (ref "U14") (pin "4") (pinfunction "FLAG_N_4") (pintype "passive+no_connect"))
    )
    (net (code "34") (name "unconnected-(U15-NC-Pad3)") (class "Default")
      (node (ref "U15") (pin "3") (pinfunction "NC_3") (pintype "passive+no_connect"))
    )
    (net (code "35") (name "unconnected-(U17-PG-Pad6)") (class "Default")
      (node (ref "U17") (pin "6") (pinfunction "PG_6") (pintype "passive+no_connect"))
    )
    (net (code "36") (name "unconnected-(U18-NC-Pad4)") (class "Default")
      (node (ref "U18") (pin "4") (pinfunction "NC_4") (pintype "passive+no_connect"))
    )
    (net (code "37") (name "unconnected-(U34-FAULT_N-Pad4)") (class "Default")
      (node (ref "U34") (pin "4") (pinfunction "FAULT_N_4") (pintype "output+no_connect"))
    )
    (net (code "38") (name "unconnected-(U35-FAULT_N-Pad4)") (class "Default")
      (node (ref "U35") (pin "4") (pinfunction "FAULT_N_4") (pintype "output+no_connect"))
    )
  )
)
